# board.net
KiCad netlist of a schematic drawn in EAGLE
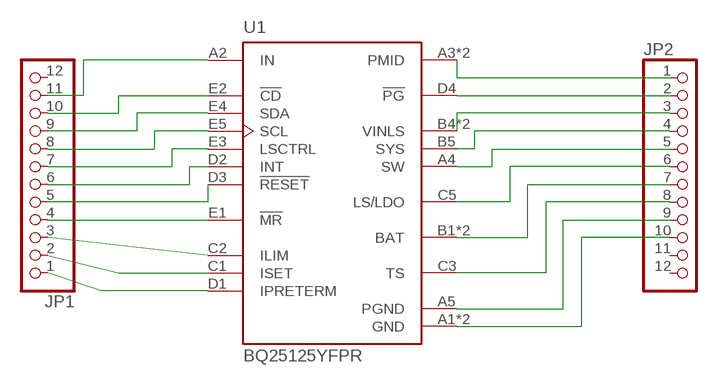
[diagram p0: schematic, sheet 1]

(export (version "E")
  (design (tool "Eeschema 10.0.6"))
  (components
    (comp (ref "JP1")
      (value "PINHD-1X12")
      (footprint "eagle-import:1X12")
      (libsource (lib "eagle-import") (part "PINHD-1X12"))
    )
    (comp (ref "JP2")
      (value "PINHD-1X12")
      (footprint "eagle-import:1X12")
      (libsource (lib "eagle-import") (part "PINHD-1X12"))
    )
    (comp (ref "U1")
      (value "BQ25125YFPR")
      (footprint "eagle-import:BGA25N40P5X5_253X247X50N")
      (fields (field (name "MF") "Texas Instruments"))
      (libsource (lib "eagle-import") (part "BQ25125YFPR"))
    )
  )
  (nets
    (net (code "1") (name "Net-(JP2-Pad1)") (class "Default")
      (node (ref "JP2") (pin "1") (pinfunction "1_1") (pintype "passive"))
      (node (ref "U1") (pin "A3") (pinfunction "PMID_A3") (pintype "bidirectional"))
      (node (ref "U1") (pin "B3") (pinfunction "PMID_B3") (pintype "bidirectional"))
    )
    (net (code "2") (name "Net-(JP2-Pad3)") (class "Default")
      (node (ref "JP2") (pin "3") (pinfunction "3_3") (pintype "passive"))
      (node (ref "U1") (pin "B4") (pinfunction "VINLS_B4") (pintype "input"))
      (node (ref "U1") (pin "C4") (pinfunction "VINLS_C4") (pintype "input"))
    )
    (net (code "3") (name "Net-(JP2-Pad7)") (class "Default")
      (node (ref "JP2") (pin "7") (pinfunction "7_7") (pintype "passive"))
      (node (ref "U1") (pin "B1") (pinfunction "BAT_B1") (pintype "bidirectional"))
      (node (ref "U1") (pin "B2") (pinfunction "BAT_B2") (pintype "bidirectional"))
    )
    (net (code "4") (name "Net-(JP2-Pad10)") (class "Default")
      (node (ref "JP2") (pin "10") (pinfunction "10_10") (pintype "passive"))
      (node (ref "U1") (pin "A1") (pinfunction "GND_A1") (pintype "power_in"))
      (node (ref "U1") (pin "D5") (pinfunction "GND_D5") (pintype "power_in"))
    )
    (net (code "5") (name "Net-(U1-ILIM)") (class "Default")
      (node (ref "JP1") (pin "3") (pinfunction "3_3") (pintype "passive"))
      (node (ref "U1") (pin "C2") (pinfunction "ILIM_C2") (pintype "input"))
    )
    (net (code "6") (name "Net-(U1-IN)") (class "Default")
      (node (ref "JP1") (pin "11") (pinfunction "11_11") (pintype "passive"))
      (node (ref "U1") (pin "A2") (pinfunction "IN_A2") (pintype "input"))
    )
    (net (code "7") (name "Net-(U1-INT)") (class "Default")
      (node (ref "JP1") (pin "6") (pinfunction "6_6") (pintype "passive"))
      (node (ref "U1") (pin "D2") (pinfunction "INT_D2") (pintype "output"))
    )
    (net (code "8") (name "Net-(U1-IPRETERM)") (class "Default")
      (node (ref "JP1") (pin "1") (pinfunction "1_1") (pintype "passive"))
      (node (ref "U1") (pin "D1") (pinfunction "IPRETERM_D1") (pintype "input"))
    )
    (net (code "9") (name "Net-(U1-ISET)") (class "Default")
      (node (ref "JP1") (pin "2") (pinfunction "2_2") (pintype "passive"))
      (node (ref "U1") (pin "C1") (pinfunction "ISET_C1") (pintype "input"))
    )
    (net (code "10") (name "Net-(U1-LSCTRL)") (class "Default")
      (node (ref "JP1") (pin "7") (pinfunction "7_7") (pintype "passive"))
      (node (ref "U1") (pin "E3") (pinfunction "LSCTRL_E3") (pintype "input"))
    )
    (net (code "11") (name "Net-(U1-LS{slash}LDO)") (class "Default")
      (node (ref "JP2") (pin "6") (pinfunction "6_6") (pintype "passive"))
      (node (ref "U1") (pin "C5") (pinfunction "LS/LDO_C5") (pintype "output"))
    )
    (net (code "12") (name "Net-(U1-PGND)") (class "Default")
      (node (ref "JP2") (pin "9") (pinfunction "9_9") (pintype "passive"))
      (node (ref "U1") (pin "A5") (pinfunction "PGND_A5") (pintype "power_in"))
    )
    (net (code "13") (name "Net-(U1-SCL)") (class "Default")
      (node (ref "JP1") (pin "8") (pinfunction "8_8") (pintype "passive"))
      (node (ref "U1") (pin "E5") (pinfunction "SCL_E5") (pintype "input"))
    )
    (net (code "14") (name "Net-(U1-SDA)") (class "Default")
      (node (ref "JP1") (pin "9") (pinfunction "9_9") (pintype "passive"))
      (node (ref "U1") (pin "E4") (pinfunction "SDA_E4") (pintype "bidirectional"))
    )
    (net (code "15") (name "Net-(U1-SW)") (class "Default")
      (node (ref "JP2") (pin "5") (pinfunction "5_5") (pintype "passive"))
      (node (ref "U1") (pin "A4") (pinfunction "SW_A4") (pintype "output"))
    )
    (net (code "16") (name "Net-(U1-SYS)") (class "Default")
      (node (ref "JP2") (pin "4") (pinfunction "4_4") (pintype "passive"))
      (node (ref "U1") (pin "B5") (pinfunction "SYS_B5") (pintype "input"))
    )
    (net (code "17") (name "Net-(U1-TS)") (class "Default")
      (node (ref "JP2") (pin "8") (pinfunction "8_8") (pintype "passive"))
      (node (ref "U1") (pin "C3") (pinfunction "TS_C3") (pintype "input"))
    )
    (net (code "18") (name "Net-(U1-~{CD})") (class "Default")
      (node (ref "JP1") (pin "10") (pinfunction "10_10") (pintype "passive"))
      (node (ref "U1") (pin "E2") (pinfunction "~{CD}_E2") (pintype "input"))
    )
    (net (code "19") (name "Net-(U1-~{MR})") (class "Default")
      (node (ref "JP1") (pin "4") (pinfunction "4_4") (pintype "passive"))
      (node (ref "U1") (pin "E1") (pinfunction "~{MR}_E1") (pintype "input"))
    )
    (net (code "20") (name "Net-(U1-~{PG})") (class "Default")
      (node (ref "JP2") (pin "2") (pinfunction "2_2") (pintype "passive"))
      (node (ref "U1") (pin "D4") (pinfunction "~{PG}_D4") (pintype "output"))
    )
    (net (code "21") (name "Net-(U1-~{RESET})") (class "Default")
      (node (ref "JP1") (pin "5") (pinfunction "5_5") (pintype "passive"))
      (node (ref "U1") (pin "D3") (pinfunction "~{RESET}_D3") (pintype "output"))
    )
    (net (code "22") (name "unconnected-(JP1-Pad12)") (class "Default")
      (node (ref "JP1") (pin "12") (pinfunction "12_12") (pintype "passive"))
    )
    (net (code "23") (name "unconnected-(JP2-Pad11)") (class "Default")
      (node (ref "JP2") (pin "11") (pinfunction "11_11") (pintype "passive"))
    )
    (net (code "24") (name "unconnected-(JP2-Pad12)") (class "Default")
      (node (ref "JP2") (pin "12") (pinfunction "12_12") (pintype "passive"))
    )
  )
)
